# BacklightCastel.net
KiCad netlist of a schematic drawn in EAGLE
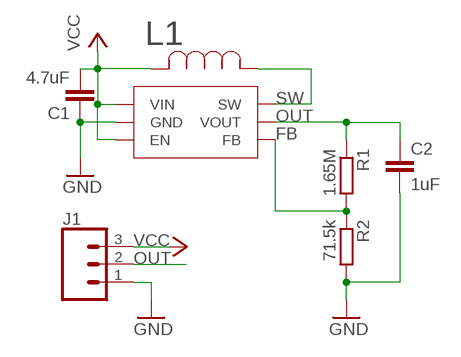
[diagram p0: schematic, sheet 1]

(export (version "E")
  (design (tool "Eeschema 10.0.6"))
  (components
    (comp (ref "C1")
      (value "4.7uF")
      (footprint "eagle-import:C0603")
      (libsource (lib "eagle-import") (part "C-EUC0603"))
    )
    (comp (ref "C2")
      (value "1uF")
      (footprint "eagle-import:C0603")
      (libsource (lib "eagle-import") (part "C-EUC0603"))
    )
    (comp (ref "J1")
      (value "CONN_03")
      (footprint "eagle-import:1X03")
      (libsource (lib "eagle-import") (part "CONN_03"))
    )
    (comp (ref "L1")
      (value "22uH")
      (footprint "eagle-import:IND_TAIYO_NRS5020")
      (fields (field (name "MANUFACTURER_PART_NUMBER") "NRS5020T220MMGJ"))
      (libsource (lib "eagle-import") (part "NRS5020T220MMGJ"))
    )
    (comp (ref "R1")
      (value "1.65M")
      (footprint "eagle-import:R0603")
      (libsource (lib "eagle-import") (part "R-EU_R0603"))
    )
    (comp (ref "R2")
      (value "71.5k")
      (footprint "eagle-import:R0603")
      (libsource (lib "eagle-import") (part "R-EU_R0603"))
    )
    (comp (ref "U1")
      (value "TLV61046A")
      (footprint "eagle-import:SOT-23-6")
      (libsource (lib "eagle-import") (part "TLV61046A"))
    )
  )
  (nets
    (net (code "1") (name "/FB") (class "Default")
      (node (ref "R1") (pin "2") (pinfunction "2_2") (pintype "passive"))
      (node (ref "R2") (pin "1") (pinfunction "1_1") (pintype "passive"))
      (node (ref "U1") (pin "3") (pinfunction "FB_3") (pintype "bidirectional"))
    )
    (net (code "2") (name "/OUT") (class "Default")
      (node (ref "C2") (pin "1") (pinfunction "1_1") (pintype "passive"))
      (node (ref "J1") (pin "2") (pinfunction "2_2") (pintype "passive"))
      (node (ref "R1") (pin "1") (pinfunction "1_1") (pintype "passive"))
      (node (ref "U1") (pin "5") (pinfunction "VOUT_5") (pintype "bidirectional"))
    )
    (net (code "3") (name "/SW") (class "Default")
      (node (ref "L1") (pin "1") (pinfunction "1_1") (pintype "passive"))
      (node (ref "U1") (pin "1") (pinfunction "SW_1") (pintype "bidirectional"))
    )
    (net (code "4") (name "GND") (class "Default")
      (node (ref "C1") (pin "1") (pinfunction "1_1") (pintype "passive"))
      (node (ref "C2") (pin "2") (pinfunction "2_2") (pintype "passive"))
      (node (ref "J1") (pin "1") (pinfunction "1_1") (pintype "passive"))
      (node (ref "R2") (pin "2") (pinfunction "2_2") (pintype "passive"))
      (node (ref "U1") (pin "2") (pinfunction "GND_2") (pintype "bidirectional"))
    )
    (net (code "5") (name "VCC") (class "Default")
      (node (ref "C1") (pin "2") (pinfunction "2_2") (pintype "passive"))
      (node (ref "J1") (pin "3") (pinfunction "3_3") (pintype "passive"))
      (node (ref "L1") (pin "2") (pinfunction "2_2") (pintype "passive"))
      (node (ref "U1") (pin "4") (pinfunction "EN_4") (pintype "bidirectional"))
      (node (ref "U1") (pin "6") (pinfunction "VIN_6") (pintype "bidirectional"))
    )
  )
)
